# DME_Board_1.net
KiCad netlist of a schematic drawn in EAGLE
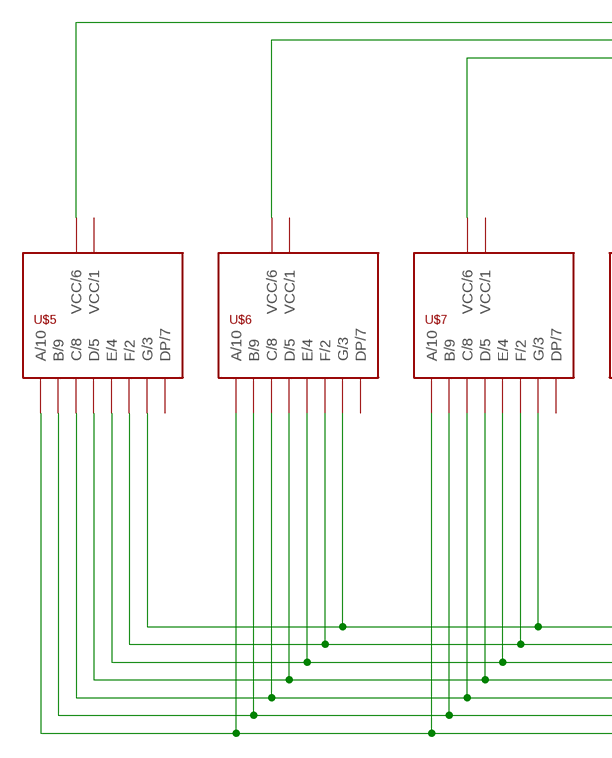
[diagram p0: schematic, sheet 1, part 1 of 2]
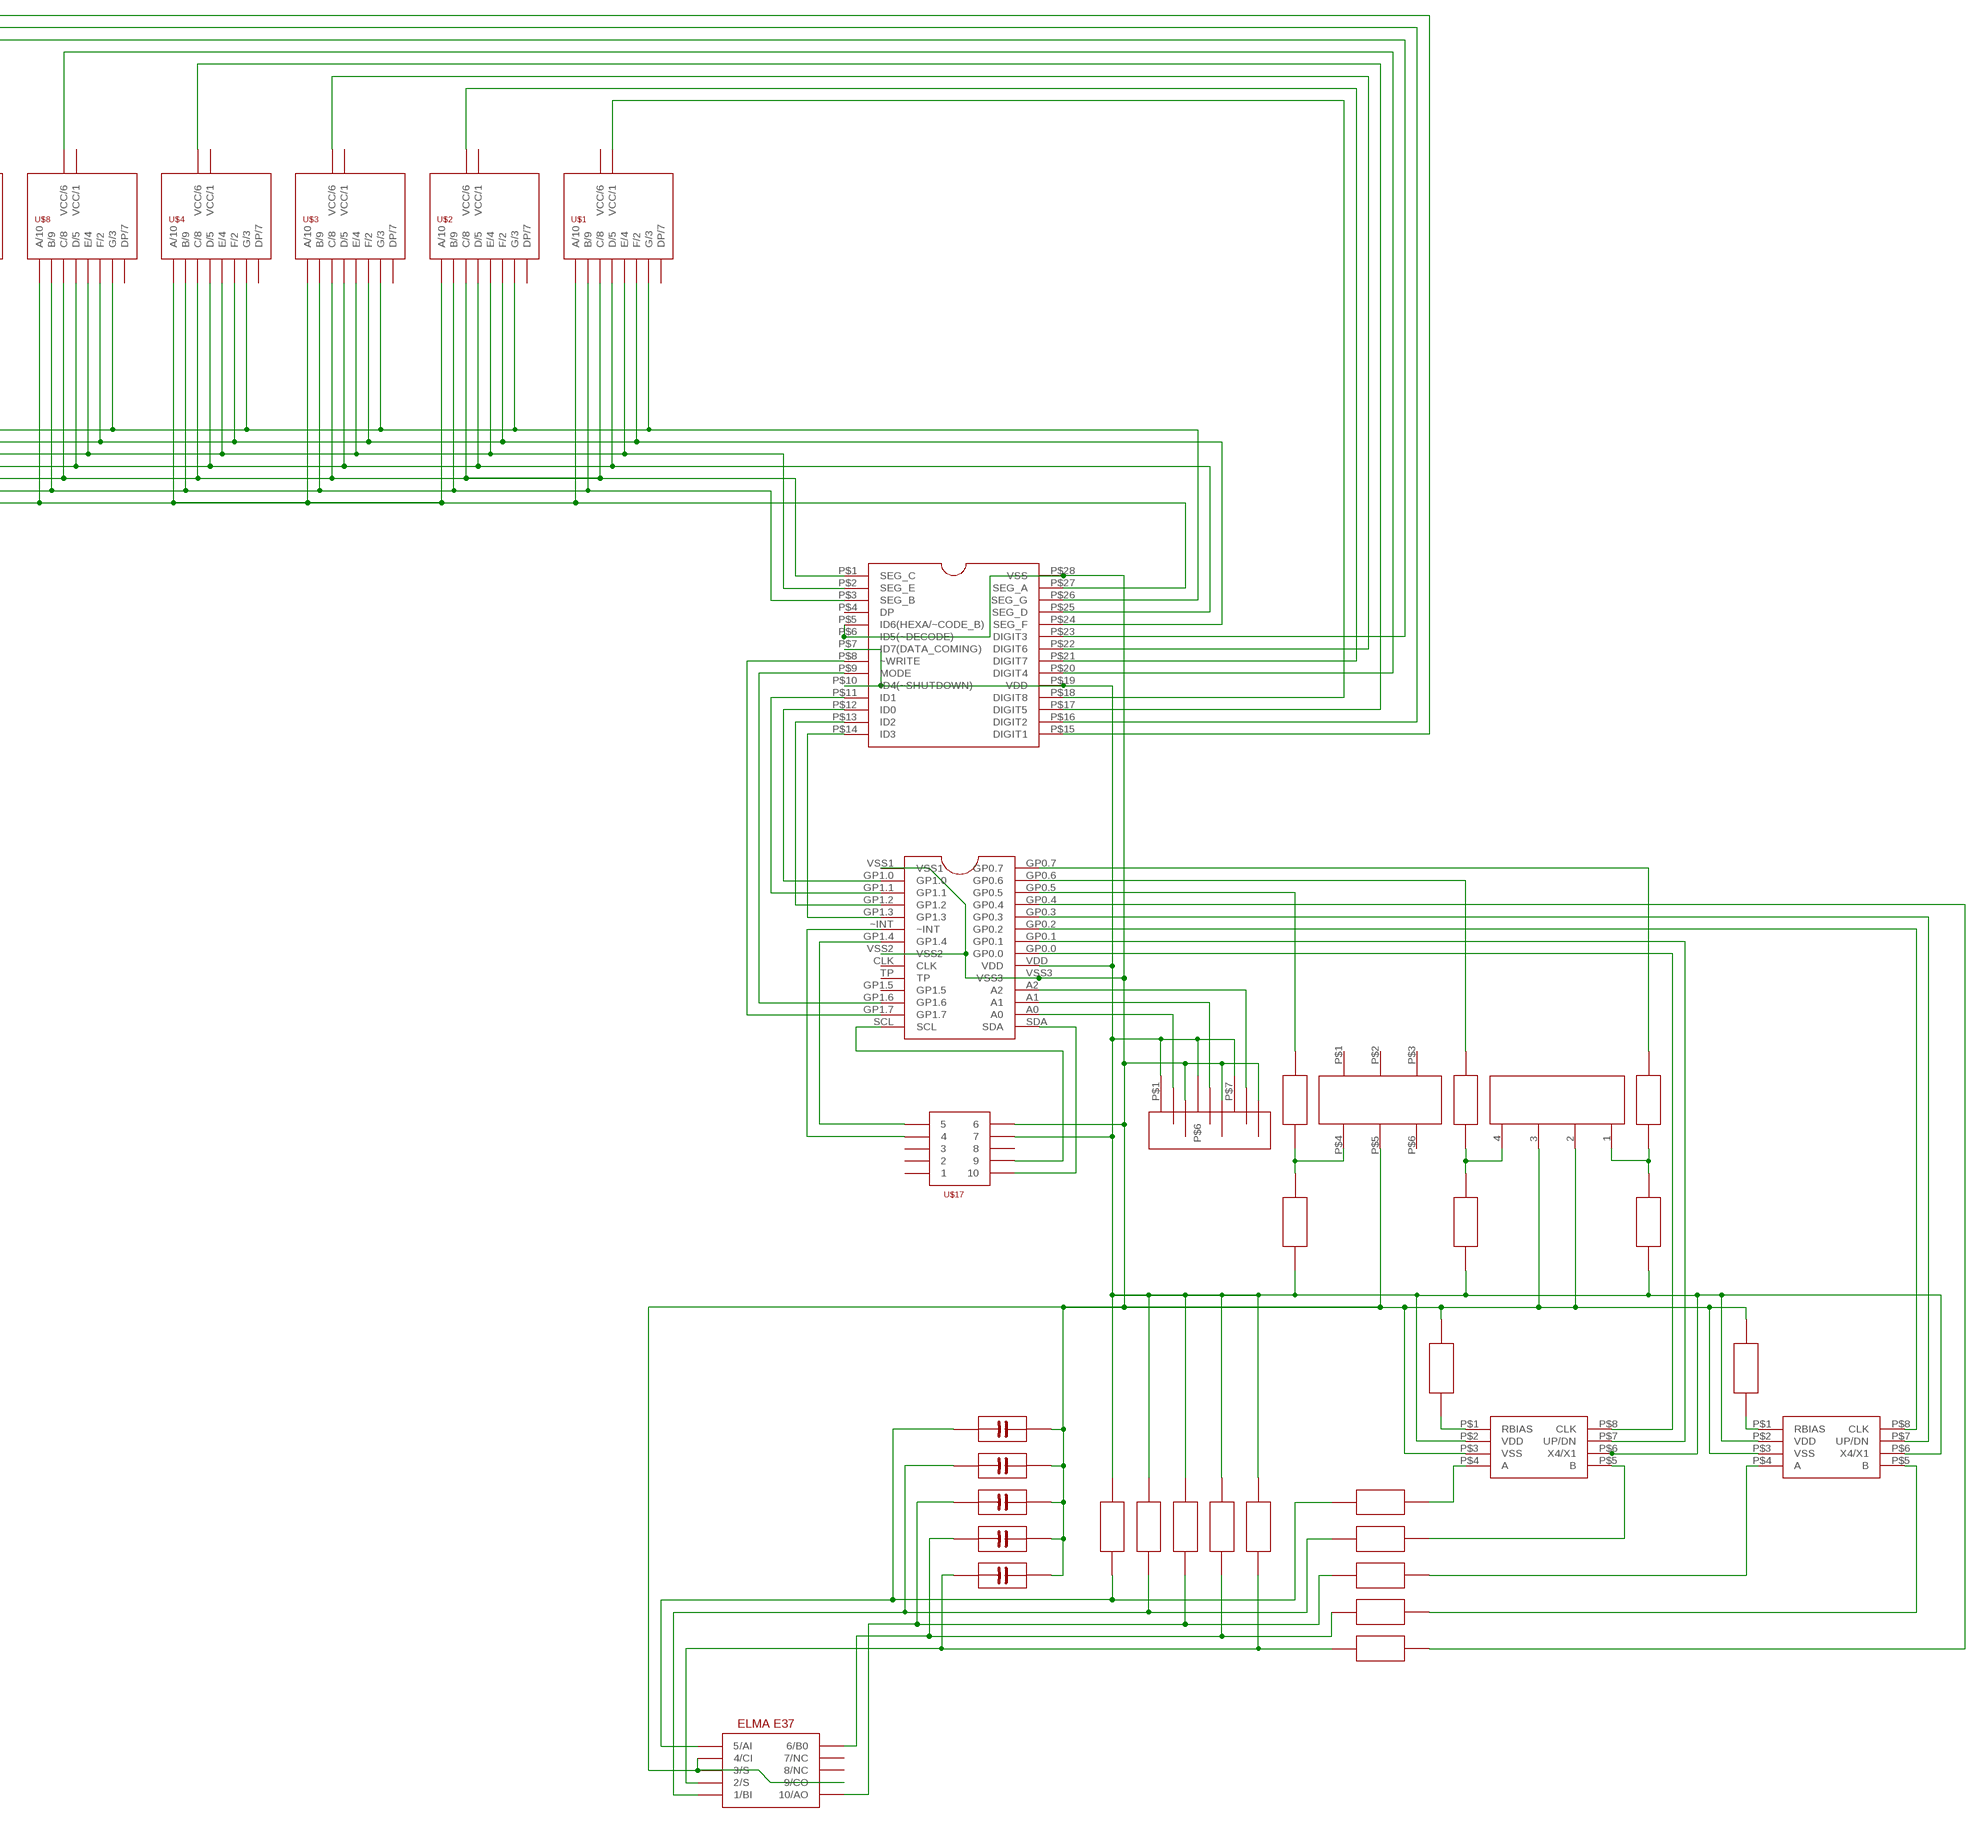
[diagram p1: schematic, sheet 1, part 2 of 2]

(export (version "E")
  (design (tool "Eeschema 10.0.6"))
  (components
    (comp (ref "U$1")
      (value "SA3611EWA")
      (footprint "eagle-import:SA3611EWA")
      (libsource (lib "eagle-import") (part "SA3611EWA"))
    )
    (comp (ref "U$2")
      (value "SA3611EWA")
      (footprint "eagle-import:SA3611EWA")
      (libsource (lib "eagle-import") (part "SA3611EWA"))
    )
    (comp (ref "U$3")
      (value "SA3611EWA")
      (footprint "eagle-import:SA3611EWA")
      (libsource (lib "eagle-import") (part "SA3611EWA"))
    )
    (comp (ref "U$4")
      (value "SA3611EWA")
      (footprint "eagle-import:SA3611EWA")
      (libsource (lib "eagle-import") (part "SA3611EWA"))
    )
    (comp (ref "U$5")
      (value "SA3611EWA")
      (footprint "eagle-import:SA3611EWA")
      (libsource (lib "eagle-import") (part "SA3611EWA"))
    )
    (comp (ref "U$6")
      (value "SA3611EWA")
      (footprint "eagle-import:SA3611EWA")
      (libsource (lib "eagle-import") (part "SA3611EWA"))
    )
    (comp (ref "U$7")
      (value "SA3611EWA")
      (footprint "eagle-import:SA3611EWA")
      (libsource (lib "eagle-import") (part "SA3611EWA"))
    )
    (comp (ref "U$8")
      (value "SA3611EWA")
      (footprint "eagle-import:SA3611EWA")
      (libsource (lib "eagle-import") (part "SA3611EWA"))
    )
    (comp (ref "U$9")
      (value "ELMA_E37")
      (footprint "eagle-import:ELMA_E37")
      (libsource (lib "eagle-import") (part "ELMA_E37"))
    )
    (comp (ref "U$10")
      (value "REZISTOR")
      (footprint "eagle-import:REZISTOR")
      (libsource (lib "eagle-import") (part "REZISTOR"))
    )
    (comp (ref "U$11")
      (value "KONDENZATOR")
      (footprint "eagle-import:KONDENZATOR")
      (libsource (lib "eagle-import") (part "KONDENZATOR"))
    )
    (comp (ref "U$12")
      (value "T220")
      (footprint "eagle-import:T220")
      (libsource (lib "eagle-import") (part "T220"))
    )
    (comp (ref "U$13")
      (value "REZISTOR")
      (footprint "eagle-import:REZISTOR")
      (libsource (lib "eagle-import") (part "REZISTOR"))
    )
    (comp (ref "U$14")
      (value "ICM7228A")
      (footprint "eagle-import:ICM7228A")
      (libsource (lib "eagle-import") (part "ICM7228A"))
    )
    (comp (ref "U$15")
      (value "REZISTOR")
      (footprint "eagle-import:REZISTOR")
      (libsource (lib "eagle-import") (part "REZISTOR"))
    )
    (comp (ref "U$16")
      (value "MCP23016")
      (footprint "eagle-import:MCP23016")
      (libsource (lib "eagle-import") (part "MCP23016"))
    )
    (comp (ref "U$17")
      (value "LISTA_2X5")
      (footprint "eagle-import:LISTA_2X5")
      (libsource (lib "eagle-import") (part "LISTA_2X5"))
    )
    (comp (ref "U$18")
      (value "LS7084")
      (footprint "eagle-import:LS7084")
      (libsource (lib "eagle-import") (part "LS7084"))
    )
    (comp (ref "U$19")
      (value "46311LD")
      (footprint "eagle-import:46311LD")
      (libsource (lib "eagle-import") (part "46311LD"))
    )
    (comp (ref "U$20")
      (value "REZISTOR")
      (footprint "eagle-import:REZISTOR")
      (libsource (lib "eagle-import") (part "REZISTOR"))
    )
    (comp (ref "U$21")
      (value "REZISTOR")
      (footprint "eagle-import:REZISTOR")
      (libsource (lib "eagle-import") (part "REZISTOR"))
    )
    (comp (ref "U$22")
      (value "REZISTOR")
      (footprint "eagle-import:REZISTOR")
      (libsource (lib "eagle-import") (part "REZISTOR"))
    )
    (comp (ref "U$23")
      (value "REZISTOR")
      (footprint "eagle-import:REZISTOR")
      (libsource (lib "eagle-import") (part "REZISTOR"))
    )
    (comp (ref "U$24")
      (value "ADRESA_0..2")
      (footprint "eagle-import:ADRESA_0..2")
      (libsource (lib "eagle-import") (part "ADRESA_0..2"))
    )
    (comp (ref "U$25")
      (value "REZISTOR")
      (footprint "eagle-import:REZISTOR")
      (libsource (lib "eagle-import") (part "REZISTOR"))
    )
    (comp (ref "U$26")
      (value "REZISTOR")
      (footprint "eagle-import:REZISTOR")
      (libsource (lib "eagle-import") (part "REZISTOR"))
    )
    (comp (ref "U$27")
      (value "REZISTOR")
      (footprint "eagle-import:REZISTOR")
      (libsource (lib "eagle-import") (part "REZISTOR"))
    )
    (comp (ref "U$28")
      (value "REZISTOR")
      (footprint "eagle-import:REZISTOR")
      (libsource (lib "eagle-import") (part "REZISTOR"))
    )
    (comp (ref "U$29")
      (value "REZISTOR")
      (footprint "eagle-import:REZISTOR")
      (libsource (lib "eagle-import") (part "REZISTOR"))
    )
    (comp (ref "U$30")
      (value "REZISTOR")
      (footprint "eagle-import:REZISTOR")
      (libsource (lib "eagle-import") (part "REZISTOR"))
    )
    (comp (ref "U$31")
      (value "REZISTOR")
      (footprint "eagle-import:REZISTOR")
      (libsource (lib "eagle-import") (part "REZISTOR"))
    )
    (comp (ref "U$32")
      (value "REZISTOR")
      (footprint "eagle-import:REZISTOR")
      (libsource (lib "eagle-import") (part "REZISTOR"))
    )
    (comp (ref "U$33")
      (value "REZISTOR")
      (footprint "eagle-import:REZISTOR")
      (libsource (lib "eagle-import") (part "REZISTOR"))
    )
    (comp (ref "U$34")
      (value "REZISTOR")
      (footprint "eagle-import:REZISTOR")
      (libsource (lib "eagle-import") (part "REZISTOR"))
    )
    (comp (ref "U$35")
      (value "REZISTOR")
      (footprint "eagle-import:REZISTOR")
      (libsource (lib "eagle-import") (part "REZISTOR"))
    )
    (comp (ref "U$42")
      (value "KONDENZATOR")
      (footprint "eagle-import:KONDENZATOR")
      (libsource (lib "eagle-import") (part "KONDENZATOR"))
    )
    (comp (ref "U$43")
      (value "KONDENZATOR")
      (footprint "eagle-import:KONDENZATOR")
      (libsource (lib "eagle-import") (part "KONDENZATOR"))
    )
    (comp (ref "U$44")
      (value "KONDENZATOR")
      (footprint "eagle-import:KONDENZATOR")
      (libsource (lib "eagle-import") (part "KONDENZATOR"))
    )
    (comp (ref "U$45")
      (value "103")
      (footprint "eagle-import:KONDENZATOR")
      (libsource (lib "eagle-import") (part "KONDENZATOR"))
    )
    (comp (ref "U$46")
      (value "LS7084")
      (footprint "eagle-import:LS7084")
      (libsource (lib "eagle-import") (part "LS7084"))
    )
  )
  (nets
    (net (code "1") (name "Net-(U$1-A{slash}10)") (class "Default")
      (node (ref "U$1") (pin "10") (pinfunction "A/10_10") (pintype "bidirectional"))
      (node (ref "U$14") (pin "P$27") (pinfunction "SEG_A_P$27") (pintype "bidirectional"))
      (node (ref "U$2") (pin "10") (pinfunction "A/10_10") (pintype "bidirectional"))
      (node (ref "U$3") (pin "10") (pinfunction "A/10_10") (pintype "bidirectional"))
      (node (ref "U$4") (pin "10") (pinfunction "A/10_10") (pintype "bidirectional"))
      (node (ref "U$5") (pin "10") (pinfunction "A/10_10") (pintype "bidirectional"))
      (node (ref "U$6") (pin "10") (pinfunction "A/10_10") (pintype "bidirectional"))
      (node (ref "U$7") (pin "10") (pinfunction "A/10_10") (pintype "bidirectional"))
      (node (ref "U$8") (pin "10") (pinfunction "A/10_10") (pintype "bidirectional"))
    )
    (net (code "2") (name "Net-(U$1-B{slash}9)") (class "Default")
      (node (ref "U$1") (pin "9") (pinfunction "B/9_9") (pintype "bidirectional"))
      (node (ref "U$14") (pin "P$3") (pinfunction "SEG_B_P$3") (pintype "bidirectional"))
      (node (ref "U$2") (pin "9") (pinfunction "B/9_9") (pintype "bidirectional"))
      (node (ref "U$3") (pin "9") (pinfunction "B/9_9") (pintype "bidirectional"))
      (node (ref "U$4") (pin "9") (pinfunction "B/9_9") (pintype "bidirectional"))
      (node (ref "U$5") (pin "9") (pinfunction "B/9_9") (pintype "bidirectional"))
      (node (ref "U$6") (pin "9") (pinfunction "B/9_9") (pintype "bidirectional"))
      (node (ref "U$7") (pin "9") (pinfunction "B/9_9") (pintype "bidirectional"))
      (node (ref "U$8") (pin "9") (pinfunction "B/9_9") (pintype "bidirectional"))
    )
    (net (code "3") (name "Net-(U$1-C{slash}8)") (class "Default")
      (node (ref "U$1") (pin "8") (pinfunction "C/8_8") (pintype "bidirectional"))
      (node (ref "U$14") (pin "P$1") (pinfunction "SEG_C_P$1") (pintype "bidirectional"))
      (node (ref "U$2") (pin "8") (pinfunction "C/8_8") (pintype "bidirectional"))
      (node (ref "U$3") (pin "8") (pinfunction "C/8_8") (pintype "bidirectional"))
      (node (ref "U$4") (pin "8") (pinfunction "C/8_8") (pintype "bidirectional"))
      (node (ref "U$5") (pin "8") (pinfunction "C/8_8") (pintype "bidirectional"))
      (node (ref "U$6") (pin "8") (pinfunction "C/8_8") (pintype "bidirectional"))
      (node (ref "U$7") (pin "8") (pinfunction "C/8_8") (pintype "bidirectional"))
      (node (ref "U$8") (pin "8") (pinfunction "C/8_8") (pintype "bidirectional"))
    )
    (net (code "4") (name "Net-(U$1-D{slash}5)") (class "Default")
      (node (ref "U$1") (pin "5") (pinfunction "D/5_5") (pintype "bidirectional"))
      (node (ref "U$14") (pin "P$25") (pinfunction "SEG_D_P$25") (pintype "bidirectional"))
      (node (ref "U$2") (pin "5") (pinfunction "D/5_5") (pintype "bidirectional"))
      (node (ref "U$3") (pin "5") (pinfunction "D/5_5") (pintype "bidirectional"))
      (node (ref "U$4") (pin "5") (pinfunction "D/5_5") (pintype "bidirectional"))
      (node (ref "U$5") (pin "5") (pinfunction "D/5_5") (pintype "bidirectional"))
      (node (ref "U$6") (pin "5") (pinfunction "D/5_5") (pintype "bidirectional"))
      (node (ref "U$7") (pin "5") (pinfunction "D/5_5") (pintype "bidirectional"))
      (node (ref "U$8") (pin "5") (pinfunction "D/5_5") (pintype "bidirectional"))
    )
    (net (code "5") (name "Net-(U$1-E{slash}4)") (class "Default")
      (node (ref "U$1") (pin "4") (pinfunction "E/4_4") (pintype "bidirectional"))
      (node (ref "U$14") (pin "P$2") (pinfunction "SEG_E_P$2") (pintype "bidirectional"))
      (node (ref "U$2") (pin "4") (pinfunction "E/4_4") (pintype "bidirectional"))
      (node (ref "U$3") (pin "4") (pinfunction "E/4_4") (pintype "bidirectional"))
      (node (ref "U$4") (pin "4") (pinfunction "E/4_4") (pintype "bidirectional"))
      (node (ref "U$5") (pin "4") (pinfunction "E/4_4") (pintype "bidirectional"))
      (node (ref "U$6") (pin "4") (pinfunction "E/4_4") (pintype "bidirectional"))
      (node (ref "U$7") (pin "4") (pinfunction "E/4_4") (pintype "bidirectional"))
      (node (ref "U$8") (pin "4") (pinfunction "E/4_4") (pintype "bidirectional"))
    )
    (net (code "6") (name "Net-(U$1-F{slash}2)") (class "Default")
      (node (ref "U$1") (pin "2") (pinfunction "F/2_2") (pintype "bidirectional"))
      (node (ref "U$14") (pin "P$24") (pinfunction "SEG_F_P$24") (pintype "bidirectional"))
      (node (ref "U$2") (pin "2") (pinfunction "F/2_2") (pintype "bidirectional"))
      (node (ref "U$3") (pin "2") (pinfunction "F/2_2") (pintype "bidirectional"))
      (node (ref "U$4") (pin "2") (pinfunction "F/2_2") (pintype "bidirectional"))
      (node (ref "U$5") (pin "2") (pinfunction "F/2_2") (pintype "bidirectional"))
      (node (ref "U$6") (pin "2") (pinfunction "F/2_2") (pintype "bidirectional"))
      (node (ref "U$7") (pin "2") (pinfunction "F/2_2") (pintype "bidirectional"))
      (node (ref "U$8") (pin "2") (pinfunction "F/2_2") (pintype "bidirectional"))
    )
    (net (code "7") (name "Net-(U$1-G{slash}3)") (class "Default")
      (node (ref "U$1") (pin "3") (pinfunction "G/3_3") (pintype "bidirectional"))
      (node (ref "U$14") (pin "P$26") (pinfunction "SEG_G_P$26") (pintype "bidirectional"))
      (node (ref "U$2") (pin "3") (pinfunction "G/3_3") (pintype "bidirectional"))
      (node (ref "U$3") (pin "3") (pinfunction "G/3_3") (pintype "bidirectional"))
      (node (ref "U$4") (pin "3") (pinfunction "G/3_3") (pintype "bidirectional"))
      (node (ref "U$5") (pin "3") (pinfunction "G/3_3") (pintype "bidirectional"))
      (node (ref "U$6") (pin "3") (pinfunction "G/3_3") (pintype "bidirectional"))
      (node (ref "U$7") (pin "3") (pinfunction "G/3_3") (pintype "bidirectional"))
      (node (ref "U$8") (pin "3") (pinfunction "G/3_3") (pintype "bidirectional"))
    )
    (net (code "8") (name "Net-(U$1-VCC{slash}1)") (class "Default")
      (node (ref "U$1") (pin "1") (pinfunction "VCC/1_1") (pintype "bidirectional"))
      (node (ref "U$14") (pin "P$18") (pinfunction "DIGIT8_P$18") (pintype "bidirectional"))
    )
    (net (code "9") (name "Net-(U$9-1{slash}BI)") (class "Default")
      (node (ref "U$11") (pin "P$1") (pinfunction "P$1_P$1") (pintype "bidirectional"))
      (node (ref "U$25") (pin "P$1") (pinfunction "P$1_P$1") (pintype "bidirectional"))
      (node (ref "U$32") (pin "P$2") (pinfunction "P$2_P$2") (pintype "bidirectional"))
      (node (ref "U$9") (pin "1") (pinfunction "1/BI_1") (pintype "bidirectional"))
    )
    (net (code "10") (name "Net-(U$9-2{slash}S)") (class "Default")
      (node (ref "U$28") (pin "P$1") (pinfunction "P$1_P$1") (pintype "bidirectional"))
      (node (ref "U$29") (pin "P$2") (pinfunction "P$2_P$2") (pintype "bidirectional"))
      (node (ref "U$45") (pin "P$1") (pinfunction "P$1_P$1") (pintype "bidirectional"))
      (node (ref "U$9") (pin "2") (pinfunction "2/S_2") (pintype "bidirectional"))
    )
    (net (code "11") (name "Net-(U$9-5{slash}AI)") (class "Default")
      (node (ref "U$20") (pin "P$1") (pinfunction "P$1_P$1") (pintype "bidirectional"))
      (node (ref "U$33") (pin "P$2") (pinfunction "P$2_P$2") (pintype "bidirectional"))
      (node (ref "U$42") (pin "P$1") (pinfunction "P$1_P$1") (pintype "bidirectional"))
      (node (ref "U$9") (pin "5") (pinfunction "5/AI_5") (pintype "bidirectional"))
    )
    (net (code "12") (name "Net-(U$9-6{slash}B0)") (class "Default")
      (node (ref "U$27") (pin "P$1") (pinfunction "P$1_P$1") (pintype "bidirectional"))
      (node (ref "U$30") (pin "P$2") (pinfunction "P$2_P$2") (pintype "bidirectional"))
      (node (ref "U$44") (pin "P$1") (pinfunction "P$1_P$1") (pintype "bidirectional"))
      (node (ref "U$9") (pin "6") (pinfunction "6/B0_6") (pintype "bidirectional"))
    )
    (net (code "13") (name "Net-(U$9-10{slash}AO)") (class "Default")
      (node (ref "U$26") (pin "P$1") (pinfunction "P$1_P$1") (pintype "bidirectional"))
      (node (ref "U$31") (pin "P$2") (pinfunction "P$2_P$2") (pintype "bidirectional"))
      (node (ref "U$43") (pin "P$1") (pinfunction "P$1_P$1") (pintype "bidirectional"))
      (node (ref "U$9") (pin "10") (pinfunction "10/AO_10") (pintype "bidirectional"))
    )
    (net (code "14") (name "Net-(U$10-PadP$2)") (class "Default")
      (node (ref "U$10") (pin "P$2") (pinfunction "P$2_P$2") (pintype "bidirectional"))
      (node (ref "U$12") (pin "P$4") (pinfunction "P$4_P$4") (pintype "bidirectional"))
      (node (ref "U$23") (pin "P$1") (pinfunction "P$1_P$1") (pintype "bidirectional"))
    )
    (net (code "15") (name "Net-(U$14-DIGIT1)") (class "Default")
      (node (ref "U$14") (pin "P$15") (pinfunction "DIGIT1_P$15") (pintype "bidirectional"))
      (node (ref "U$5") (pin "6") (pinfunction "VCC/6_6") (pintype "bidirectional"))
    )
    (net (code "16") (name "Net-(U$14-DIGIT2)") (class "Default")
      (node (ref "U$14") (pin "P$16") (pinfunction "DIGIT2_P$16") (pintype "bidirectional"))
      (node (ref "U$6") (pin "6") (pinfunction "VCC/6_6") (pintype "bidirectional"))
    )
    (net (code "17") (name "Net-(U$14-DIGIT3)") (class "Default")
      (node (ref "U$14") (pin "P$23") (pinfunction "DIGIT3_P$23") (pintype "bidirectional"))
      (node (ref "U$7") (pin "6") (pinfunction "VCC/6_6") (pintype "bidirectional"))
    )
    (net (code "18") (name "Net-(U$14-DIGIT4)") (class "Default")
      (node (ref "U$14") (pin "P$20") (pinfunction "DIGIT4_P$20") (pintype "bidirectional"))
      (node (ref "U$8") (pin "6") (pinfunction "VCC/6_6") (pintype "bidirectional"))
    )
    (net (code "19") (name "Net-(U$14-DIGIT5)") (class "Default")
      (node (ref "U$14") (pin "P$17") (pinfunction "DIGIT5_P$17") (pintype "bidirectional"))
      (node (ref "U$4") (pin "6") (pinfunction "VCC/6_6") (pintype "bidirectional"))
    )
    (net (code "20") (name "Net-(U$14-DIGIT6)") (class "Default")
      (node (ref "U$14") (pin "P$22") (pinfunction "DIGIT6_P$22") (pintype "bidirectional"))
      (node (ref "U$3") (pin "6") (pinfunction "VCC/6_6") (pintype "bidirectional"))
    )
    (net (code "21") (name "Net-(U$14-DIGIT7)") (class "Default")
      (node (ref "U$14") (pin "P$21") (pinfunction "DIGIT7_P$21") (pintype "bidirectional"))
      (node (ref "U$2") (pin "6") (pinfunction "VCC/6_6") (pintype "bidirectional"))
    )
    (net (code "22") (name "Net-(U$14-ID0)") (class "Default")
      (node (ref "U$14") (pin "P$12") (pinfunction "ID0_P$12") (pintype "bidirectional"))
      (node (ref "U$16") (pin "GP1.0") (pinfunction "GP1.0_GP1.0") (pintype "bidirectional"))
    )
    (net (code "23") (name "Net-(U$14-ID1)") (class "Default")
      (node (ref "U$14") (pin "P$11") (pinfunction "ID1_P$11") (pintype "bidirectional"))
      (node (ref "U$16") (pin "GP1.1") (pinfunction "GP1.1_GP1.1") (pintype "bidirectional"))
    )
    (net (code "24") (name "Net-(U$14-ID2)") (class "Default")
      (node (ref "U$14") (pin "P$13") (pinfunction "ID2_P$13") (pintype "bidirectional"))
      (node (ref "U$16") (pin "GP1.2") (pinfunction "GP1.2_GP1.2") (pintype "bidirectional"))
    )
    (net (code "25") (name "Net-(U$14-ID3)") (class "Default")
      (node (ref "U$14") (pin "P$14") (pinfunction "ID3_P$14") (pintype "bidirectional"))
      (node (ref "U$16") (pin "GP1.3") (pinfunction "GP1.3_GP1.3") (pintype "bidirectional"))
    )
    (net (code "26") (name "Net-(U$14-ID4(~{SHUTDOWN}))") (class "Default")
      (node (ref "U$10") (pin "P$1") (pinfunction "P$1_P$1") (pintype "bidirectional"))
      (node (ref "U$13") (pin "P$1") (pinfunction "P$1_P$1") (pintype "bidirectional"))
      (node (ref "U$14") (pin "P$10") (pinfunction "ID4(~{SHUTDOWN})_P$10") (pintype "bidirectional"))
      (node (ref "U$14") (pin "P$19") (pinfunction "VDD_P$19") (pintype "bidirectional"))
      (node (ref "U$14") (pin "P$7") (pinfunction "ID7(DATA_COMING)_P$7") (pintype "bidirectional"))
      (node (ref "U$15") (pin "P$1") (pinfunction "P$1_P$1") (pintype "bidirectional"))
      (node (ref "U$16") (pin "VDD") (pinfunction "VDD_VDD") (pintype "bidirectional"))
      (node (ref "U$17") (pin "7") (pinfunction "7_7") (pintype "bidirectional"))
      (node (ref "U$18") (pin "P$2") (pinfunction "VDD_P$2") (pintype "bidirectional"))
      (node (ref "U$18") (pin "P$6") (pinfunction "X4/X1_P$6") (pintype "bidirectional"))
      (node (ref "U$20") (pin "P$2") (pinfunction "P$2_P$2") (pintype "bidirectional"))
      (node (ref "U$24") (pin "P$1") (pinfunction "P$1_P$1") (pintype "bidirectional"))
      (node (ref "U$24") (pin "P$6") (pinfunction "P$6_P$6") (pintype "bidirectional"))
      (node (ref "U$24") (pin "P$7") (pinfunction "P$7_P$7") (pintype "bidirectional"))
      (node (ref "U$25") (pin "P$2") (pinfunction "P$2_P$2") (pintype "bidirectional"))
      (node (ref "U$26") (pin "P$2") (pinfunction "P$2_P$2") (pintype "bidirectional"))
      (node (ref "U$27") (pin "P$2") (pinfunction "P$2_P$2") (pintype "bidirectional"))
      (node (ref "U$28") (pin "P$2") (pinfunction "P$2_P$2") (pintype "bidirectional"))
      (node (ref "U$46") (pin "P$2") (pinfunction "VDD_P$2") (pintype "bidirectional"))
      (node (ref "U$46") (pin "P$6") (pinfunction "X4/X1_P$6") (pintype "bidirectional"))
    )
    (net (code "27") (name "Net-(U$14-ID5(~{DECODE}))") (class "Default")
      (node (ref "U$11") (pin "P$2") (pinfunction "P$2_P$2") (pintype "bidirectional"))
      (node (ref "U$12") (pin "P$5") (pinfunction "P$5_P$5") (pintype "bidirectional"))
      (node (ref "U$14") (pin "P$28") (pinfunction "VSS_P$28") (pintype "bidirectional"))
      (node (ref "U$14") (pin "P$5") (pinfunction "ID6(HEXA/~{CODE_B})_P$5") (pintype "bidirectional"))
      (node (ref "U$14") (pin "P$6") (pinfunction "ID5(~{DECODE})_P$6") (pintype "bidirectional"))
      (node (ref "U$16") (pin "VSS1") (pinfunction "VSS1_VSS1") (pintype "bidirectional"))
      (node (ref "U$16") (pin "VSS2") (pinfunction "VSS2_VSS2") (pintype "bidirectional"))
      (node (ref "U$16") (pin "VSS3") (pinfunction "VSS3_VSS3") (pintype "bidirectional"))
      (node (ref "U$17") (pin "6") (pinfunction "6_6") (pintype "bidirectional"))
      (node (ref "U$18") (pin "P$3") (pinfunction "VSS_P$3") (pintype "bidirectional"))
      (node (ref "U$19") (pin "2") (pinfunction "P$2_2") (pintype "bidirectional"))
      (node (ref "U$19") (pin "3") (pinfunction "P$3_3") (pintype "bidirectional"))
      (node (ref "U$24") (pin "P$3") (pinfunction "P$3_P$3") (pintype "bidirectional"))
      (node (ref "U$24") (pin "P$4") (pinfunction "P$4_P$4") (pintype "bidirectional"))
      (node (ref "U$24") (pin "P$9") (pinfunction "P$9_P$9") (pintype "bidirectional"))
      (node (ref "U$34") (pin "P$2") (pinfunction "P$2_P$2") (pintype "bidirectional"))
      (node (ref "U$35") (pin "P$2") (pinfunction "P$2_P$2") (pintype "bidirectional"))
      (node (ref "U$42") (pin "P$2") (pinfunction "P$2_P$2") (pintype "bidirectional"))
      (node (ref "U$43") (pin "P$2") (pinfunction "P$2_P$2") (pintype "bidirectional"))
      (node (ref "U$44") (pin "P$2") (pinfunction "P$2_P$2") (pintype "bidirectional"))
      (node (ref "U$45") (pin "P$2") (pinfunction "P$2_P$2") (pintype "bidirectional"))
      (node (ref "U$46") (pin "P$3") (pinfunction "VSS_P$3") (pintype "bidirectional"))
      (node (ref "U$9") (pin "3") (pinfunction "3/S_3") (pintype "bidirectional"))
      (node (ref "U$9") (pin "4") (pinfunction "4/CI_4") (pintype "bidirectional"))
      (node (ref "U$9") (pin "9") (pinfunction "9/CO_9") (pintype "bidirectional"))
    )
    (net (code "28") (name "Net-(U$14-MODE)") (class "Default")
      (node (ref "U$14") (pin "P$9") (pinfunction "MODE_P$9") (pintype "bidirectional"))
      (node (ref "U$16") (pin "GP1.6") (pinfunction "GP1.6_GP1.6") (pintype "bidirectional"))
    )
    (net (code "29") (name "Net-(U$14-~{WRITE})") (class "Default")
      (node (ref "U$14") (pin "P$8") (pinfunction "~{WRITE}_P$8") (pintype "bidirectional"))
      (node (ref "U$16") (pin "GP1.7") (pinfunction "GP1.7_GP1.7") (pintype "bidirectional"))
    )
    (net (code "30") (name "Net-(U$16-PadA0)") (class "Default")
      (node (ref "U$16") (pin "A0") (pinfunction "A0_A0") (pintype "bidirectional"))
      (node (ref "U$24") (pin "P$2") (pinfunction "P$2_P$2") (pintype "bidirectional"))
    )
    (net (code "31") (name "Net-(U$16-PadA1)") (class "Default")
      (node (ref "U$16") (pin "A1") (pinfunction "A1_A1") (pintype "bidirectional"))
      (node (ref "U$24") (pin "P$5") (pinfunction "P$5_P$5") (pintype "bidirectional"))
    )
    (net (code "32") (name "Net-(U$16-PadA2)") (class "Default")
      (node (ref "U$16") (pin "A2") (pinfunction "A2_A2") (pintype "bidirectional"))
      (node (ref "U$24") (pin "P$8") (pinfunction "P$8_P$8") (pintype "bidirectional"))
    )
    (net (code "33") (name "Net-(U$16-PadGP0.4)") (class "Default")
      (node (ref "U$16") (pin "GP0.4") (pinfunction "GP0.4_GP0.4") (pintype "bidirectional"))
      (node (ref "U$29") (pin "P$1") (pinfunction "P$1_P$1") (pintype "bidirectional"))
    )
    (net (code "34") (name "Net-(U$16-PadGP0.5)") (class "Default")
      (node (ref "U$16") (pin "GP0.5") (pinfunction "GP0.5_GP0.5") (pintype "bidirectional"))
      (node (ref "U$23") (pin "P$2") (pinfunction "P$2_P$2") (pintype "bidirectional"))
    )
    (net (code "35") (name "Net-(U$16-PadGP0.6)") (class "Default")
      (node (ref "U$16") (pin "GP0.6") (pinfunction "GP0.6_GP0.6") (pintype "bidirectional"))
      (node (ref "U$22") (pin "P$2") (pinfunction "P$2_P$2") (pintype "bidirectional"))
    )
    (net (code "36") (name "Net-(U$16-PadGP0.7)") (class "Default")
      (node (ref "U$16") (pin "GP0.7") (pinfunction "GP0.7_GP0.7") (pintype "bidirectional"))
      (node (ref "U$21") (pin "P$2") (pinfunction "P$2_P$2") (pintype "bidirectional"))
    )
    (net (code "37") (name "Net-(U$16-PadGP1.4)") (class "Default")
      (node (ref "U$16") (pin "GP1.4") (pinfunction "GP1.4_GP1.4") (pintype "bidirectional"))
      (node (ref "U$17") (pin "5") (pinfunction "5_5") (pintype "bidirectional"))
    )
    (net (code "38") (name "Net-(U$16-PadSCL)") (class "Default")
      (node (ref "U$16") (pin "SCL") (pinfunction "SCL_SCL") (pintype "bidirectional"))
      (node (ref "U$17") (pin "9") (pinfunction "9_9") (pintype "bidirectional"))
    )
    (net (code "39") (name "Net-(U$16-PadSDA)") (class "Default")
      (node (ref "U$16") (pin "SDA") (pinfunction "SDA_SDA") (pintype "bidirectional"))
      (node (ref "U$17") (pin "10") (pinfunction "10_10") (pintype "bidirectional"))
    )
    (net (code "40") (name "Net-(U$16-~{INT})") (class "Default")
      (node (ref "U$16") (pin "~INT") (pinfunction "~{INT}_~INT") (pintype "bidirectional"))
      (node (ref "U$17") (pin "4") (pinfunction "4_4") (pintype "bidirectional"))
    )
    (net (code "41") (name "Net-(U$18-A)") (class "Default")
      (node (ref "U$18") (pin "P$4") (pinfunction "A_P$4") (pintype "bidirectional"))
      (node (ref "U$33") (pin "P$1") (pinfunction "P$1_P$1") (pintype "bidirectional"))
    )
    (net (code "42") (name "Net-(U$18-B)") (class "Default")
      (node (ref "U$18") (pin "P$5") (pinfunction "B_P$5") (pintype "bidirectional"))
      (node (ref "U$32") (pin "P$1") (pinfunction "P$1_P$1") (pintype "bidirectional"))
    )
    (net (code "43") (name "Net-(U$18-CLK)") (class "Default")
      (node (ref "U$16") (pin "GP0.0") (pinfunction "GP0.0_GP0.0") (pintype "bidirectional"))
      (node (ref "U$18") (pin "P$8") (pinfunction "CLK_P$8") (pintype "bidirectional"))
    )
    (net (code "44") (name "Net-(U$18-RBIAS)") (class "Default")
      (node (ref "U$18") (pin "P$1") (pinfunction "RBIAS_P$1") (pintype "bidirectional"))
      (node (ref "U$34") (pin "P$1") (pinfunction "P$1_P$1") (pintype "bidirectional"))
    )
    (net (code "45") (name "Net-(U$18-UP{slash}DN)") (class "Default")
      (node (ref "U$16") (pin "GP0.1") (pinfunction "GP0.1_GP0.1") (pintype "bidirectional"))
      (node (ref "U$18") (pin "P$7") (pinfunction "UP/DN_P$7") (pintype "bidirectional"))
    )
    (net (code "46") (name "Net-(U$19-P$1)") (class "Default")
      (node (ref "U$15") (pin "P$2") (pinfunction "P$2_P$2") (pintype "bidirectional"))
      (node (ref "U$19") (pin "1") (pinfunction "P$1_1") (pintype "bidirectional"))
      (node (ref "U$21") (pin "P$1") (pinfunction "P$1_P$1") (pintype "bidirectional"))
    )
    (net (code "47") (name "Net-(U$19-P$4)") (class "Default")
      (node (ref "U$13") (pin "P$2") (pinfunction "P$2_P$2") (pintype "bidirectional"))
      (node (ref "U$19") (pin "4") (pinfunction "P$4_4") (pintype "bidirectional"))
      (node (ref "U$22") (pin "P$1") (pinfunction "P$1_P$1") (pintype "bidirectional"))
    )
    (net (code "48") (name "Net-(U$46-A)") (class "Default")
      (node (ref "U$31") (pin "P$1") (pinfunction "P$1_P$1") (pintype "bidirectional"))
      (node (ref "U$46") (pin "P$4") (pinfunction "A_P$4") (pintype "bidirectional"))
    )
    (net (code "49") (name "Net-(U$46-B)") (class "Default")
      (node (ref "U$30") (pin "P$1") (pinfunction "P$1_P$1") (pintype "bidirectional"))
      (node (ref "U$46") (pin "P$5") (pinfunction "B_P$5") (pintype "bidirectional"))
    )
    (net (code "50") (name "Net-(U$46-CLK)") (class "Default")
      (node (ref "U$16") (pin "GP0.2") (pinfunction "GP0.2_GP0.2") (pintype "bidirectional"))
      (node (ref "U$46") (pin "P$8") (pinfunction "CLK_P$8") (pintype "bidirectional"))
    )
    (net (code "51") (name "Net-(U$46-RBIAS)") (class "Default")
      (node (ref "U$35") (pin "P$1") (pinfunction "P$1_P$1") (pintype "bidirectional"))
      (node (ref "U$46") (pin "P$1") (pinfunction "RBIAS_P$1") (pintype "bidirectional"))
    )
    (net (code "52") (name "Net-(U$46-UP{slash}DN)") (class "Default")
      (node (ref "U$16") (pin "GP0.3") (pinfunction "GP0.3_GP0.3") (pintype "bidirectional"))
      (node (ref "U$46") (pin "P$7") (pinfunction "UP/DN_P$7") (pintype "bidirectional"))
    )
    (net (code "53") (name "unconnected-(U$1-DP{slash}7-Pad7)") (class "Default")
      (node (ref "U$1") (pin "7") (pinfunction "DP/7_7") (pintype "bidirectional"))
    )
    (net (code "54") (name "unconnected-(U$1-VCC{slash}6-Pad6)") (class "Default")
      (node (ref "U$1") (pin "6") (pinfunction "VCC/6_6") (pintype "bidirectional"))
    )
    (net (code "55") (name "unconnected-(U$2-DP{slash}7-Pad7)") (class "Default")
      (node (ref "U$2") (pin "7") (pinfunction "DP/7_7") (pintype "bidirectional"))
    )
    (net (code "56") (name "unconnected-(U$2-VCC{slash}1-Pad1)") (class "Default")
      (node (ref "U$2") (pin "1") (pinfunction "VCC/1_1") (pintype "bidirectional"))
    )
    (net (code "57") (name "unconnected-(U$3-DP{slash}7-Pad7)") (class "Default")
      (node (ref "U$3") (pin "7") (pinfunction "DP/7_7") (pintype "bidirectional"))
    )
    (net (code "58") (name "unconnected-(U$3-VCC{slash}1-Pad1)") (class "Default")
      (node (ref "U$3") (pin "1") (pinfunction "VCC/1_1") (pintype "bidirectional"))
    )
    (net (code "59") (name "unconnected-(U$4-DP{slash}7-Pad7)") (class "Default")
      (node (ref "U$4") (pin "7") (pinfunction "DP/7_7") (pintype "bidirectional"))
    )
    (net (code "60") (name "unconnected-(U$4-VCC{slash}1-Pad1)") (class "Default")
      (node (ref "U$4") (pin "1") (pinfunction "VCC/1_1") (pintype "bidirectional"))
    )
    (net (code "61") (name "unconnected-(U$5-DP{slash}7-Pad7)") (class "Default")
      (node (ref "U$5") (pin "7") (pinfunction "DP/7_7") (pintype "bidirectional"))
    )
    (net (code "62") (name "unconnected-(U$5-VCC{slash}1-Pad1)") (class "Default")
      (node (ref "U$5") (pin "1") (pinfunction "VCC/1_1") (pintype "bidirectional"))
    )
    (net (code "63") (name "unconnected-(U$6-DP{slash}7-Pad7)") (class "Default")
      (node (ref "U$6") (pin "7") (pinfunction "DP/7_7") (pintype "bidirectional"))
    )
    (net (code "64") (name "unconnected-(U$6-VCC{slash}1-Pad1)") (class "Default")
      (node (ref "U$6") (pin "1") (pinfunction "VCC/1_1") (pintype "bidirectional"))
    )
    (net (code "65") (name "unconnected-(U$7-DP{slash}7-Pad7)") (class "Default")
      (node (ref "U$7") (pin "7") (pinfunction "DP/7_7") (pintype "bidirectional"))
    )
    (net (code "66") (name "unconnected-(U$7-VCC{slash}1-Pad1)") (class "Default")
      (node (ref "U$7") (pin "1") (pinfunction "VCC/1_1") (pintype "bidirectional"))
    )
    (net (code "67") (name "unconnected-(U$8-DP{slash}7-Pad7)") (class "Default")
      (node (ref "U$8") (pin "7") (pinfunction "DP/7_7") (pintype "bidirectional"))
    )
    (net (code "68") (name "unconnected-(U$8-VCC{slash}1-Pad1)") (class "Default")
      (node (ref "U$8") (pin "1") (pinfunction "VCC/1_1") (pintype "bidirectional"))
    )
    (net (code "69") (name "unconnected-(U$9-7{slash}NC-Pad7)") (class "Default")
      (node (ref "U$9") (pin "7") (pinfunction "7/NC_7") (pintype "bidirectional"))
    )
    (net (code "70") (name "unconnected-(U$9-8{slash}NC-Pad8)") (class "Default")
      (node (ref "U$9") (pin "8") (pinfunction "8/NC_8") (pintype "bidirectional"))
    )
    (net (code "71") (name "unconnected-(U$12-PadP$1)") (class "Default")
      (node (ref "U$12") (pin "P$1") (pinfunction "P$1_P$1") (pintype "bidirectional"))
    )
    (net (code "72") (name "unconnected-(U$12-PadP$2)") (class "Default")
      (node (ref "U$12") (pin "P$2") (pinfunction "P$2_P$2") (pintype "bidirectional"))
    )
    (net (code "73") (name "unconnected-(U$12-PadP$3)") (class "Default")
      (node (ref "U$12") (pin "P$3") (pinfunction "P$3_P$3") (pintype "bidirectional"))
    )
    (net (code "74") (name "unconnected-(U$12-PadP$6)") (class "Default")
      (node (ref "U$12") (pin "P$6") (pinfunction "P$6_P$6") (pintype "bidirectional"))
    )
    (net (code "75") (name "unconnected-(U$14-DP-PadP$4)") (class "Default")
      (node (ref "U$14") (pin "P$4") (pinfunction "DP_P$4") (pintype "bidirectional"))
    )
    (net (code "76") (name "unconnected-(U$16-PadCLK)") (class "Default")
      (node (ref "U$16") (pin "CLK") (pinfunction "CLK_CLK") (pintype "bidirectional"))
    )
    (net (code "77") (name "unconnected-(U$16-PadGP1.5)") (class "Default")
      (node (ref "U$16") (pin "GP1.5") (pinfunction "GP1.5_GP1.5") (pintype "bidirectional"))
    )
    (net (code "78") (name "unconnected-(U$16-PadTP)") (class "Default")
      (node (ref "U$16") (pin "TP") (pinfunction "TP_TP") (pintype "bidirectional"))
    )
    (net (code "79") (name "unconnected-(U$17-Pad1)") (class "Default")
      (node (ref "U$17") (pin "1") (pinfunction "1_1") (pintype "bidirectional"))
    )
    (net (code "80") (name "unconnected-(U$17-Pad2)") (class "Default")
      (node (ref "U$17") (pin "2") (pinfunction "2_2") (pintype "bidirectional"))
    )
    (net (code "81") (name "unconnected-(U$17-Pad3)") (class "Default")
      (node (ref "U$17") (pin "3") (pinfunction "3_3") (pintype "bidirectional"))
    )
    (net (code "82") (name "unconnected-(U$17-Pad8)") (class "Default")
      (node (ref "U$17") (pin "8") (pinfunction "8_8") (pintype "bidirectional"))
    )
  )
)
